# E5SB12_0000F20S33.net
KiCad netlist of a schematic drawn in Altium Designer
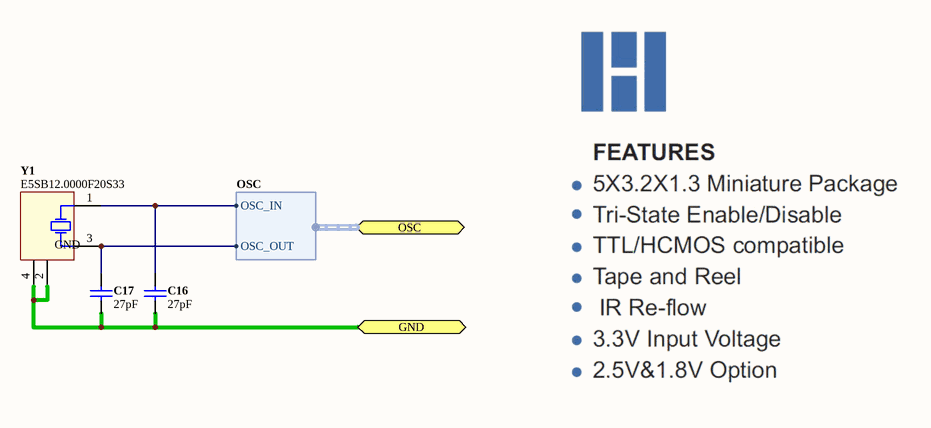
[diagram p0: E5SB12.0000F20S33.SchDoc]

(export (version "E")
  (design (tool "Eeschema 10.0.6"))
  (components
    (comp (ref "C16")
      (value "27pF")
      (footprint "CAPC0402(1005)60_N")
      (description "CAP 27pF 50V ±5% 0402 (1005 Metric) Thickness 0.6mm SMD")
      (fields (field (name "TOLERANCE") "±5%") (field (name "Comment") "CAP 27pF 50V 0402(1005)"))
      (libsource (lib "Altium Content Vault") (part "CMP-1034-00963-1"))
    )
    (comp (ref "C17")
      (value "27pF")
      (footprint "CAPC0402(1005)60_N")
      (description "CAP 27pF 50V ±5% 0402 (1005 Metric) Thickness 0.6mm SMD")
      (fields (field (name "TOLERANCE") "±5%") (field (name "Comment") "CAP 27pF 50V 0402(1005)"))
      (libsource (lib "Altium Content Vault") (part "CMP-1034-00963-1"))
    )
    (comp (ref "Y1")
      (value "E5SB12.0000F20S33")
      (footprint "HOSC-L500HW320H105-4")
      (description "Crystal, SMD, 12MHz, 10.0pF")
      (libsource (lib "Altium Content Vault") (part "CMP-5195-00000-1"))
    )
  )
  (nets
    (net (code "2") (name "/GND") (class "Default")
      (node (ref "C16") (pin "2") (pinfunction "2_2") (pintype "passive"))
      (node (ref "C17") (pin "2") (pinfunction "2_2") (pintype "passive"))
      (node (ref "Y1") (pin "2") (pinfunction "GND_2") (pintype "power_in"))
      (node (ref "Y1") (pin "4") (pinfunction "GND_4") (pintype "power_in"))
    )
    (net (code "4") (name "Net-(Y1-X1)") (class "Default")
      (node (ref "C16") (pin "1") (pinfunction "1_1") (pintype "passive"))
      (node (ref "Y1") (pin "1") (pinfunction "X1_1") (pintype "passive"))
    )
    (net (code "5") (name "Net-(Y1-X2)") (class "Default")
      (node (ref "C17") (pin "1") (pinfunction "1_1") (pintype "passive"))
      (node (ref "Y1") (pin "3") (pinfunction "X2_3") (pintype "passive"))
    )
  )
)
